# buttons.net
KiCad netlist of a schematic drawn in EAGLE
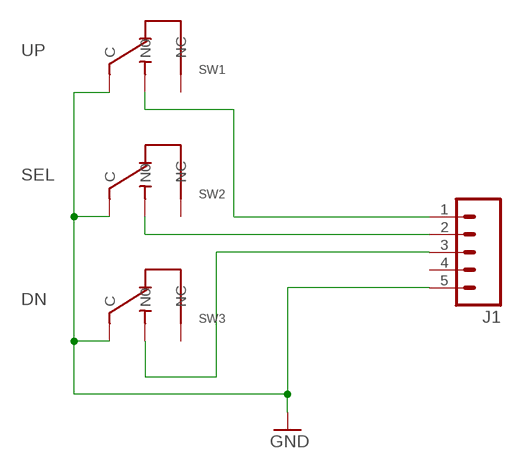
[diagram p0: schematic, sheet 1]

(export (version "E")
  (design (tool "Eeschema 10.0.6"))
  (components
    (comp (ref "J1")
      (value "M05PTH")
      (footprint "eagle-import:1X05")
      (libsource (lib "eagle-import") (part "M05PTH"))
    )
    (comp (ref "SW1")
      (value "MICROSWITCH")
      (footprint "eagle-import:MICROSWITCH")
      (libsource (lib "eagle-import") (part "MICROSWITCH"))
    )
    (comp (ref "SW2")
      (value "MICROSWITCH")
      (footprint "eagle-import:MICROSWITCH")
      (libsource (lib "eagle-import") (part "MICROSWITCH"))
    )
    (comp (ref "SW3")
      (value "MICROSWITCH")
      (footprint "eagle-import:MICROSWITCH")
      (libsource (lib "eagle-import") (part "MICROSWITCH"))
    )
  )
  (nets
    (net (code "1") (name "GND") (class "Default")
      (node (ref "J1") (pin "5") (pinfunction "5_5") (pintype "passive"))
      (node (ref "SW1") (pin "C") (pinfunction "C_C") (pintype "bidirectional"))
      (node (ref "SW2") (pin "C") (pinfunction "C_C") (pintype "bidirectional"))
      (node (ref "SW3") (pin "C") (pinfunction "C_C") (pintype "bidirectional"))
    )
    (net (code "2") (name "Net-(SW1-N0)") (class "Default")
      (node (ref "J1") (pin "1") (pinfunction "1_1") (pintype "passive"))
      (node (ref "SW1") (pin "NO") (pinfunction "N0_NO") (pintype "bidirectional"))
    )
    (net (code "3") (name "Net-(SW2-N0)") (class "Default")
      (node (ref "J1") (pin "2") (pinfunction "2_2") (pintype "passive"))
      (node (ref "SW2") (pin "NO") (pinfunction "N0_NO") (pintype "bidirectional"))
    )
    (net (code "4") (name "Net-(SW3-N0)") (class "Default")
      (node (ref "J1") (pin "3") (pinfunction "3_3") (pintype "passive"))
      (node (ref "SW3") (pin "NO") (pinfunction "N0_NO") (pintype "bidirectional"))
    )
    (net (code "5") (name "unconnected-(J1-Pad4)") (class "Default")
      (node (ref "J1") (pin "4") (pinfunction "4_4") (pintype "passive"))
    )
    (net (code "6") (name "unconnected-(SW1-PadNC)") (class "Default")
      (node (ref "SW1") (pin "NC") (pinfunction "NC_NC") (pintype "bidirectional"))
    )
    (net (code "7") (name "unconnected-(SW2-PadNC)") (class "Default")
      (node (ref "SW2") (pin "NC") (pinfunction "NC_NC") (pintype "bidirectional"))
    )
    (net (code "8") (name "unconnected-(SW3-PadNC)") (class "Default")
      (node (ref "SW3") (pin "NC") (pinfunction "NC_NC") (pintype "bidirectional"))
    )
  )
)
